# leds.net
KiCad netlist of a schematic drawn in EAGLE
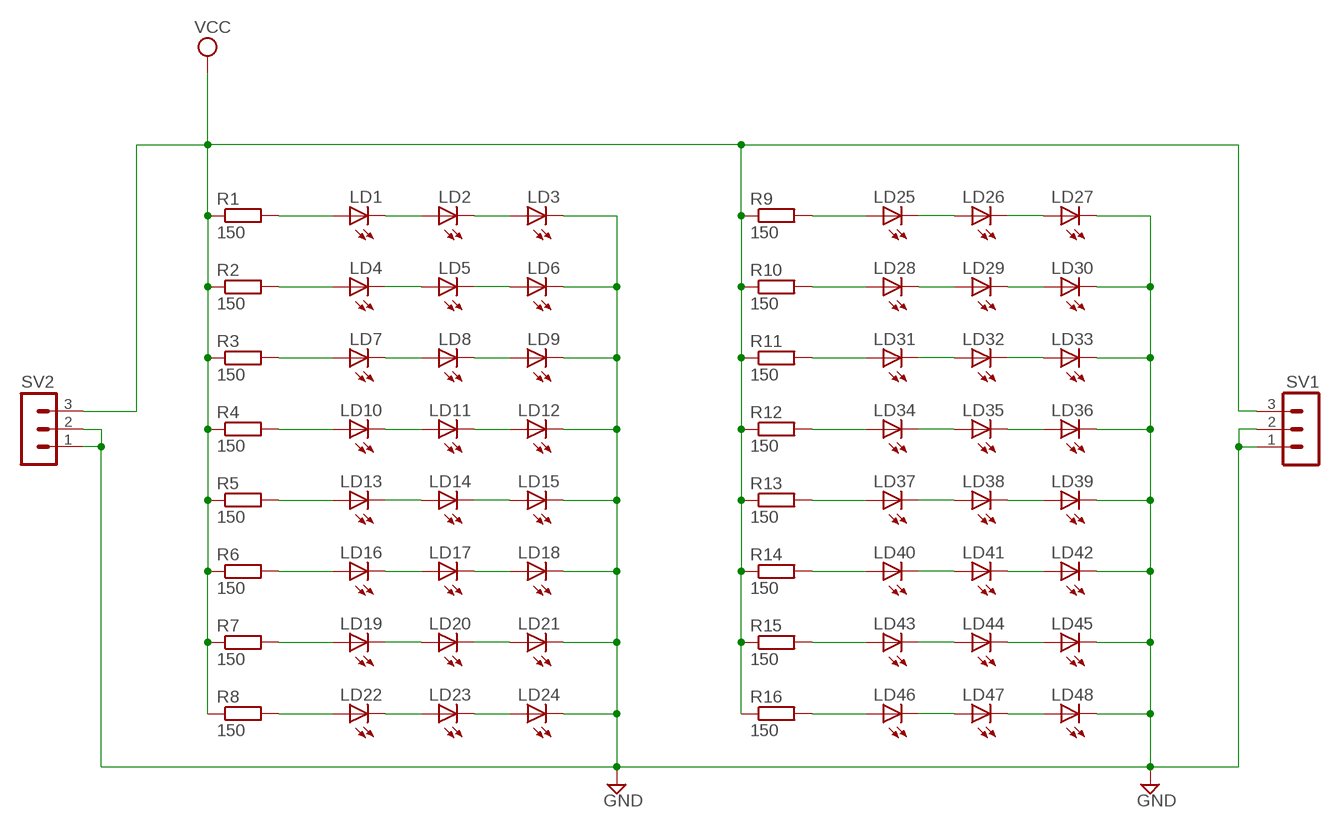
[diagram p0: schematic, sheet 1]

(export (version "E")
  (design (tool "Eeschema 10.0.6"))
  (components
    (comp (ref "LD1")
      (value "LED5MM")
      (footprint "eagle-import:LED5MM")
      (libsource (lib "eagle-import") (part "LED5MM"))
    )
    (comp (ref "LD2")
      (value "LED5MM")
      (footprint "eagle-import:LED5MM")
      (libsource (lib "eagle-import") (part "LED5MM"))
    )
    (comp (ref "LD3")
      (value "LED5MM")
      (footprint "eagle-import:LED5MM")
      (libsource (lib "eagle-import") (part "LED5MM"))
    )
    (comp (ref "LD4")
      (value "LED5MM")
      (footprint "eagle-import:LED5MM")
      (libsource (lib "eagle-import") (part "LED5MM"))
    )
    (comp (ref "LD5")
      (value "LED5MM")
      (footprint "eagle-import:LED5MM")
      (libsource (lib "eagle-import") (part "LED5MM"))
    )
    (comp (ref "LD6")
      (value "LED5MM")
      (footprint "eagle-import:LED5MM")
      (libsource (lib "eagle-import") (part "LED5MM"))
    )
    (comp (ref "LD7")
      (value "LED5MM")
      (footprint "eagle-import:LED5MM")
      (libsource (lib "eagle-import") (part "LED5MM"))
    )
    (comp (ref "LD8")
      (value "LED5MM")
      (footprint "eagle-import:LED5MM")
      (libsource (lib "eagle-import") (part "LED5MM"))
    )
    (comp (ref "LD9")
      (value "LED5MM")
      (footprint "eagle-import:LED5MM")
      (libsource (lib "eagle-import") (part "LED5MM"))
    )
    (comp (ref "LD10")
      (value "LED5MM")
      (footprint "eagle-import:LED5MM")
      (libsource (lib "eagle-import") (part "LED5MM"))
    )
    (comp (ref "LD11")
      (value "LED5MM")
      (footprint "eagle-import:LED5MM")
      (libsource (lib "eagle-import") (part "LED5MM"))
    )
    (comp (ref "LD12")
      (value "LED5MM")
      (footprint "eagle-import:LED5MM")
      (libsource (lib "eagle-import") (part "LED5MM"))
    )
    (comp (ref "LD13")
      (value "LED5MM")
      (footprint "eagle-import:LED5MM")
      (libsource (lib "eagle-import") (part "LED5MM"))
    )
    (comp (ref "LD14")
      (value "LED5MM")
      (footprint "eagle-import:LED5MM")
      (libsource (lib "eagle-import") (part "LED5MM"))
    )
    (comp (ref "LD15")
      (value "LED5MM")
      (footprint "eagle-import:LED5MM")
      (libsource (lib "eagle-import") (part "LED5MM"))
    )
    (comp (ref "LD16")
      (value "LED5MM")
      (footprint "eagle-import:LED5MM")
      (libsource (lib "eagle-import") (part "LED5MM"))
    )
    (comp (ref "LD17")
      (value "LED5MM")
      (footprint "eagle-import:LED5MM")
      (libsource (lib "eagle-import") (part "LED5MM"))
    )
    (comp (ref "LD18")
      (value "LED5MM")
      (footprint "eagle-import:LED5MM")
      (libsource (lib "eagle-import") (part "LED5MM"))
    )
    (comp (ref "LD19")
      (value "LED5MM")
      (footprint "eagle-import:LED5MM")
      (libsource (lib "eagle-import") (part "LED5MM"))
    )
    (comp (ref "LD20")
      (value "LED5MM")
      (footprint "eagle-import:LED5MM")
      (libsource (lib "eagle-import") (part "LED5MM"))
    )
    (comp (ref "LD21")
      (value "LED5MM")
      (footprint "eagle-import:LED5MM")
      (libsource (lib "eagle-import") (part "LED5MM"))
    )
    (comp (ref "LD22")
      (value "LED5MM")
      (footprint "eagle-import:LED5MM")
      (libsource (lib "eagle-import") (part "LED5MM"))
    )
    (comp (ref "LD23")
      (value "LED5MM")
      (footprint "eagle-import:LED5MM")
      (libsource (lib "eagle-import") (part "LED5MM"))
    )
    (comp (ref "LD24")
      (value "LED5MM")
      (footprint "eagle-import:LED5MM")
      (libsource (lib "eagle-import") (part "LED5MM"))
    )
    (comp (ref "LD25")
      (value "LED5MM")
      (footprint "eagle-import:LED5MM")
      (libsource (lib "eagle-import") (part "LED5MM"))
    )
    (comp (ref "LD26")
      (value "LED5MM")
      (footprint "eagle-import:LED5MM")
      (libsource (lib "eagle-import") (part "LED5MM"))
    )
    (comp (ref "LD27")
      (value "LED5MM")
      (footprint "eagle-import:LED5MM")
      (libsource (lib "eagle-import") (part "LED5MM"))
    )
    (comp (ref "LD28")
      (value "LED5MM")
      (footprint "eagle-import:LED5MM")
      (libsource (lib "eagle-import") (part "LED5MM"))
    )
    (comp (ref "LD29")
      (value "LED5MM")
      (footprint "eagle-import:LED5MM")
      (libsource (lib "eagle-import") (part "LED5MM"))
    )
    (comp (ref "LD30")
      (value "LED5MM")
      (footprint "eagle-import:LED5MM")
      (libsource (lib "eagle-import") (part "LED5MM"))
    )
    (comp (ref "LD31")
      (value "LED5MM")
      (footprint "eagle-import:LED5MM")
      (libsource (lib "eagle-import") (part "LED5MM"))
    )
    (comp (ref "LD32")
      (value "LED5MM")
      (footprint "eagle-import:LED5MM")
      (libsource (lib "eagle-import") (part "LED5MM"))
    )
    (comp (ref "LD33")
      (value "LED5MM")
      (footprint "eagle-import:LED5MM")
      (libsource (lib "eagle-import") (part "LED5MM"))
    )
    (comp (ref "LD34")
      (value "LED5MM")
      (footprint "eagle-import:LED5MM")
      (libsource (lib "eagle-import") (part "LED5MM"))
    )
    (comp (ref "LD35")
      (value "LED5MM")
      (footprint "eagle-import:LED5MM")
      (libsource (lib "eagle-import") (part "LED5MM"))
    )
    (comp (ref "LD36")
      (value "LED5MM")
      (footprint "eagle-import:LED5MM")
      (libsource (lib "eagle-import") (part "LED5MM"))
    )
    (comp (ref "LD37")
      (value "LED5MM")
      (footprint "eagle-import:LED5MM")
      (libsource (lib "eagle-import") (part "LED5MM"))
    )
    (comp (ref "LD38")
      (value "LED5MM")
      (footprint "eagle-import:LED5MM")
      (libsource (lib "eagle-import") (part "LED5MM"))
    )
    (comp (ref "LD39")
      (value "LED5MM")
      (footprint "eagle-import:LED5MM")
      (libsource (lib "eagle-import") (part "LED5MM"))
    )
    (comp (ref "LD40")
      (value "LED5MM")
      (footprint "eagle-import:LED5MM")
      (libsource (lib "eagle-import") (part "LED5MM"))
    )
    (comp (ref "LD41")
      (value "LED5MM")
      (footprint "eagle-import:LED5MM")
      (libsource (lib "eagle-import") (part "LED5MM"))
    )
    (comp (ref "LD42")
      (value "LED5MM")
      (footprint "eagle-import:LED5MM")
      (libsource (lib "eagle-import") (part "LED5MM"))
    )
    (comp (ref "LD43")
      (value "LED5MM")
      (footprint "eagle-import:LED5MM")
      (libsource (lib "eagle-import") (part "LED5MM"))
    )
    (comp (ref "LD44")
      (value "LED5MM")
      (footprint "eagle-import:LED5MM")
      (libsource (lib "eagle-import") (part "LED5MM"))
    )
    (comp (ref "LD45")
      (value "LED5MM")
      (footprint "eagle-import:LED5MM")
      (libsource (lib "eagle-import") (part "LED5MM"))
    )
    (comp (ref "LD46")
      (value "LED5MM")
      (footprint "eagle-import:LED5MM")
      (libsource (lib "eagle-import") (part "LED5MM"))
    )
    (comp (ref "LD47")
      (value "LED5MM")
      (footprint "eagle-import:LED5MM")
      (libsource (lib "eagle-import") (part "LED5MM"))
    )
    (comp (ref "LD48")
      (value "LED5MM")
      (footprint "eagle-import:LED5MM")
      (libsource (lib "eagle-import") (part "LED5MM"))
    )
    (comp (ref "R1")
      (value "150")
      (footprint "eagle-import:0204_7")
      (libsource (lib "eagle-import") (part "R-EU_0204/7"))
    )
    (comp (ref "R2")
      (value "150")
      (footprint "eagle-import:0204_7")
      (libsource (lib "eagle-import") (part "R-EU_0204/7"))
    )
    (comp (ref "R3")
      (value "150")
      (footprint "eagle-import:0204_7")
      (libsource (lib "eagle-import") (part "R-EU_0204/7"))
    )
    (comp (ref "R4")
      (value "150")
      (footprint "eagle-import:0204_7")
      (libsource (lib "eagle-import") (part "R-EU_0204/7"))
    )
    (comp (ref "R5")
      (value "150")
      (footprint "eagle-import:0204_7")
      (libsource (lib "eagle-import") (part "R-EU_0204/7"))
    )
    (comp (ref "R6")
      (value "150")
      (footprint "eagle-import:0204_7")
      (libsource (lib "eagle-import") (part "R-EU_0204/7"))
    )
    (comp (ref "R7")
      (value "150")
      (footprint "eagle-import:0204_7")
      (libsource (lib "eagle-import") (part "R-EU_0204/7"))
    )
    (comp (ref "R8")
      (value "150")
      (footprint "eagle-import:0204_7")
      (libsource (lib "eagle-import") (part "R-EU_0204/7"))
    )
    (comp (ref "R9")
      (value "150")
      (footprint "eagle-import:0204_7")
      (libsource (lib "eagle-import") (part "R-EU_0204/7"))
    )
    (comp (ref "R10")
      (value "150")
      (footprint "eagle-import:0204_7")
      (libsource (lib "eagle-import") (part "R-EU_0204/7"))
    )
    (comp (ref "R11")
      (value "150")
      (footprint "eagle-import:0204_7")
      (libsource (lib "eagle-import") (part "R-EU_0204/7"))
    )
    (comp (ref "R12")
      (value "150")
      (footprint "eagle-import:0204_7")
      (libsource (lib "eagle-import") (part "R-EU_0204/7"))
    )
    (comp (ref "R13")
      (value "150")
      (footprint "eagle-import:0204_7")
      (libsource (lib "eagle-import") (part "R-EU_0204/7"))
    )
    (comp (ref "R14")
      (value "150")
      (footprint "eagle-import:0204_7")
      (libsource (lib "eagle-import") (part "R-EU_0204/7"))
    )
    (comp (ref "R15")
      (value "150")
      (footprint "eagle-import:0204_7")
      (libsource (lib "eagle-import") (part "R-EU_0204/7"))
    )
    (comp (ref "R16")
      (value "150")
      (footprint "eagle-import:0204_7")
      (libsource (lib "eagle-import") (part "R-EU_0204/7"))
    )
    (comp (ref "SV1")
      (value "MA03-1")
      (footprint "eagle-import:MA03-1")
      (libsource (lib "eagle-import") (part "MA03-1"))
    )
    (comp (ref "SV2")
      (value "MA03-1")
      (footprint "eagle-import:MA03-1")
      (libsource (lib "eagle-import") (part "MA03-1"))
    )
  )
  (nets
    (net (code "1") (name "GND") (class "Default")
      (node (ref "LD12") (pin "K") (pinfunction "C_K") (pintype "passive"))
      (node (ref "LD15") (pin "K") (pinfunction "C_K") (pintype "passive"))
      (node (ref "LD18") (pin "K") (pinfunction "C_K") (pintype "passive"))
      (node (ref "LD21") (pin "K") (pinfunction "C_K") (pintype "passive"))
      (node (ref "LD24") (pin "K") (pinfunction "C_K") (pintype "passive"))
      (node (ref "LD27") (pin "K") (pinfunction "C_K") (pintype "passive"))
      (node (ref "LD3") (pin "K") (pinfunction "C_K") (pintype "passive"))
      (node (ref "LD30") (pin "K") (pinfunction "C_K") (pintype "passive"))
      (node (ref "LD33") (pin "K") (pinfunction "C_K") (pintype "passive"))
      (node (ref "LD36") (pin "K") (pinfunction "C_K") (pintype "passive"))
      (node (ref "LD39") (pin "K") (pinfunction "C_K") (pintype "passive"))
      (node (ref "LD42") (pin "K") (pinfunction "C_K") (pintype "passive"))
      (node (ref "LD45") (pin "K") (pinfunction "C_K") (pintype "passive"))
      (node (ref "LD48") (pin "K") (pinfunction "C_K") (pintype "passive"))
      (node (ref "LD6") (pin "K") (pinfunction "C_K") (pintype "passive"))
      (node (ref "LD9") (pin "K") (pinfunction "C_K") (pintype "passive"))
      (node (ref "SV1") (pin "1") (pinfunction "1_1") (pintype "passive"))
      (node (ref "SV1") (pin "2") (pinfunction "2_2") (pintype "passive"))
      (node (ref "SV2") (pin "1") (pinfunction "1_1") (pintype "passive"))
      (node (ref "SV2") (pin "2") (pinfunction "2_2") (pintype "passive"))
    )
    (net (code "2") (name "Net-(LD1-C)") (class "Default")
      (node (ref "LD1") (pin "K") (pinfunction "C_K") (pintype "passive"))
      (node (ref "LD2") (pin "A") (pinfunction "A_A") (pintype "passive"))
    )
    (net (code "3") (name "Net-(LD1-PadA)") (class "Default")
      (node (ref "LD1") (pin "A") (pinfunction "A_A") (pintype "passive"))
      (node (ref "R1") (pin "2") (pinfunction "2_2") (pintype "passive"))
    )
    (net (code "4") (name "Net-(LD2-C)") (class "Default")
      (node (ref "LD2") (pin "K") (pinfunction "C_K") (pintype "passive"))
      (node (ref "LD3") (pin "A") (pinfunction "A_A") (pintype "passive"))
    )
    (net (code "5") (name "Net-(LD4-C)") (class "Default")
      (node (ref "LD4") (pin "K") (pinfunction "C_K") (pintype "passive"))
      (node (ref "LD5") (pin "A") (pinfunction "A_A") (pintype "passive"))
    )
    (net (code "6") (name "Net-(LD4-PadA)") (class "Default")
      (node (ref "LD4") (pin "A") (pinfunction "A_A") (pintype "passive"))
      (node (ref "R2") (pin "2") (pinfunction "2_2") (pintype "passive"))
    )
    (net (code "7") (name "Net-(LD5-C)") (class "Default")
      (node (ref "LD5") (pin "K") (pinfunction "C_K") (pintype "passive"))
      (node (ref "LD6") (pin "A") (pinfunction "A_A") (pintype "passive"))
    )
    (net (code "8") (name "Net-(LD7-C)") (class "Default")
      (node (ref "LD7") (pin "K") (pinfunction "C_K") (pintype "passive"))
      (node (ref "LD8") (pin "A") (pinfunction "A_A") (pintype "passive"))
    )
    (net (code "9") (name "Net-(LD7-PadA)") (class "Default")
      (node (ref "LD7") (pin "A") (pinfunction "A_A") (pintype "passive"))
      (node (ref "R3") (pin "2") (pinfunction "2_2") (pintype "passive"))
    )
    (net (code "10") (name "Net-(LD8-C)") (class "Default")
      (node (ref "LD8") (pin "K") (pinfunction "C_K") (pintype "passive"))
      (node (ref "LD9") (pin "A") (pinfunction "A_A") (pintype "passive"))
    )
    (net (code "11") (name "Net-(LD10-C)") (class "Default")
      (node (ref "LD10") (pin "K") (pinfunction "C_K") (pintype "passive"))
      (node (ref "LD11") (pin "A") (pinfunction "A_A") (pintype "passive"))
    )
    (net (code "12") (name "Net-(LD10-PadA)") (class "Default")
      (node (ref "LD10") (pin "A") (pinfunction "A_A") (pintype "passive"))
      (node (ref "R4") (pin "2") (pinfunction "2_2") (pintype "passive"))
    )
    (net (code "13") (name "Net-(LD11-C)") (class "Default")
      (node (ref "LD11") (pin "K") (pinfunction "C_K") (pintype "passive"))
      (node (ref "LD12") (pin "A") (pinfunction "A_A") (pintype "passive"))
    )
    (net (code "14") (name "Net-(LD13-C)") (class "Default")
      (node (ref "LD13") (pin "K") (pinfunction "C_K") (pintype "passive"))
      (node (ref "LD14") (pin "A") (pinfunction "A_A") (pintype "passive"))
    )
    (net (code "15") (name "Net-(LD13-PadA)") (class "Default")
      (node (ref "LD13") (pin "A") (pinfunction "A_A") (pintype "passive"))
      (node (ref "R5") (pin "2") (pinfunction "2_2") (pintype "passive"))
    )
    (net (code "16") (name "Net-(LD14-C)") (class "Default")
      (node (ref "LD14") (pin "K") (pinfunction "C_K") (pintype "passive"))
      (node (ref "LD15") (pin "A") (pinfunction "A_A") (pintype "passive"))
    )
    (net (code "17") (name "Net-(LD16-C)") (class "Default")
      (node (ref "LD16") (pin "K") (pinfunction "C_K") (pintype "passive"))
      (node (ref "LD17") (pin "A") (pinfunction "A_A") (pintype "passive"))
    )
    (net (code "18") (name "Net-(LD16-PadA)") (class "Default")
      (node (ref "LD16") (pin "A") (pinfunction "A_A") (pintype "passive"))
      (node (ref "R6") (pin "2") (pinfunction "2_2") (pintype "passive"))
    )
    (net (code "19") (name "Net-(LD17-C)") (class "Default")
      (node (ref "LD17") (pin "K") (pinfunction "C_K") (pintype "passive"))
      (node (ref "LD18") (pin "A") (pinfunction "A_A") (pintype "passive"))
    )
    (net (code "20") (name "Net-(LD19-C)") (class "Default")
      (node (ref "LD19") (pin "K") (pinfunction "C_K") (pintype "passive"))
      (node (ref "LD20") (pin "A") (pinfunction "A_A") (pintype "passive"))
    )
    (net (code "21") (name "Net-(LD19-PadA)") (class "Default")
      (node (ref "LD19") (pin "A") (pinfunction "A_A") (pintype "passive"))
      (node (ref "R7") (pin "2") (pinfunction "2_2") (pintype "passive"))
    )
    (net (code "22") (name "Net-(LD20-C)") (class "Default")
      (node (ref "LD20") (pin "K") (pinfunction "C_K") (pintype "passive"))
      (node (ref "LD21") (pin "A") (pinfunction "A_A") (pintype "passive"))
    )
    (net (code "23") (name "Net-(LD22-C)") (class "Default")
      (node (ref "LD22") (pin "K") (pinfunction "C_K") (pintype "passive"))
      (node (ref "LD23") (pin "A") (pinfunction "A_A") (pintype "passive"))
    )
    (net (code "24") (name "Net-(LD22-PadA)") (class "Default")
      (node (ref "LD22") (pin "A") (pinfunction "A_A") (pintype "passive"))
      (node (ref "R8") (pin "2") (pinfunction "2_2") (pintype "passive"))
    )
    (net (code "25") (name "Net-(LD23-C)") (class "Default")
      (node (ref "LD23") (pin "K") (pinfunction "C_K") (pintype "passive"))
      (node (ref "LD24") (pin "A") (pinfunction "A_A") (pintype "passive"))
    )
    (net (code "26") (name "Net-(LD25-C)") (class "Default")
      (node (ref "LD25") (pin "K") (pinfunction "C_K") (pintype "passive"))
      (node (ref "LD26") (pin "A") (pinfunction "A_A") (pintype "passive"))
    )
    (net (code "27") (name "Net-(LD25-PadA)") (class "Default")
      (node (ref "LD25") (pin "A") (pinfunction "A_A") (pintype "passive"))
      (node (ref "R9") (pin "2") (pinfunction "2_2") (pintype "passive"))
    )
    (net (code "28") (name "Net-(LD26-C)") (class "Default")
      (node (ref "LD26") (pin "K") (pinfunction "C_K") (pintype "passive"))
      (node (ref "LD27") (pin "A") (pinfunction "A_A") (pintype "passive"))
    )
    (net (code "29") (name "Net-(LD28-C)") (class "Default")
      (node (ref "LD28") (pin "K") (pinfunction "C_K") (pintype "passive"))
      (node (ref "LD29") (pin "A") (pinfunction "A_A") (pintype "passive"))
    )
    (net (code "30") (name "Net-(LD28-PadA)") (class "Default")
      (node (ref "LD28") (pin "A") (pinfunction "A_A") (pintype "passive"))
      (node (ref "R10") (pin "2") (pinfunction "2_2") (pintype "passive"))
    )
    (net (code "31") (name "Net-(LD29-C)") (class "Default")
      (node (ref "LD29") (pin "K") (pinfunction "C_K") (pintype "passive"))
      (node (ref "LD30") (pin "A") (pinfunction "A_A") (pintype "passive"))
    )
    (net (code "32") (name "Net-(LD31-C)") (class "Default")
      (node (ref "LD31") (pin "K") (pinfunction "C_K") (pintype "passive"))
      (node (ref "LD32") (pin "A") (pinfunction "A_A") (pintype "passive"))
    )
    (net (code "33") (name "Net-(LD31-PadA)") (class "Default")
      (node (ref "LD31") (pin "A") (pinfunction "A_A") (pintype "passive"))
      (node (ref "R11") (pin "2") (pinfunction "2_2") (pintype "passive"))
    )
    (net (code "34") (name "Net-(LD32-C)") (class "Default")
      (node (ref "LD32") (pin "K") (pinfunction "C_K") (pintype "passive"))
      (node (ref "LD33") (pin "A") (pinfunction "A_A") (pintype "passive"))
    )
    (net (code "35") (name "Net-(LD34-C)") (class "Default")
      (node (ref "LD34") (pin "K") (pinfunction "C_K") (pintype "passive"))
      (node (ref "LD35") (pin "A") (pinfunction "A_A") (pintype "passive"))
    )
    (net (code "36") (name "Net-(LD34-PadA)") (class "Default")
      (node (ref "LD34") (pin "A") (pinfunction "A_A") (pintype "passive"))
      (node (ref "R12") (pin "2") (pinfunction "2_2") (pintype "passive"))
    )
    (net (code "37") (name "Net-(LD35-C)") (class "Default")
      (node (ref "LD35") (pin "K") (pinfunction "C_K") (pintype "passive"))
      (node (ref "LD36") (pin "A") (pinfunction "A_A") (pintype "passive"))
    )
    (net (code "38") (name "Net-(LD37-C)") (class "Default")
      (node (ref "LD37") (pin "K") (pinfunction "C_K") (pintype "passive"))
      (node (ref "LD38") (pin "A") (pinfunction "A_A") (pintype "passive"))
    )
    (net (code "39") (name "Net-(LD37-PadA)") (class "Default")
      (node (ref "LD37") (pin "A") (pinfunction "A_A") (pintype "passive"))
      (node (ref "R13") (pin "2") (pinfunction "2_2") (pintype "passive"))
    )
    (net (code "40") (name "Net-(LD38-C)") (class "Default")
      (node (ref "LD38") (pin "K") (pinfunction "C_K") (pintype "passive"))
      (node (ref "LD39") (pin "A") (pinfunction "A_A") (pintype "passive"))
    )
    (net (code "41") (name "Net-(LD40-C)") (class "Default")
      (node (ref "LD40") (pin "K") (pinfunction "C_K") (pintype "passive"))
      (node (ref "LD41") (pin "A") (pinfunction "A_A") (pintype "passive"))
    )
    (net (code "42") (name "Net-(LD40-PadA)") (class "Default")
      (node (ref "LD40") (pin "A") (pinfunction "A_A") (pintype "passive"))
      (node (ref "R14") (pin "2") (pinfunction "2_2") (pintype "passive"))
    )
    (net (code "43") (name "Net-(LD41-C)") (class "Default")
      (node (ref "LD41") (pin "K") (pinfunction "C_K") (pintype "passive"))
      (node (ref "LD42") (pin "A") (pinfunction "A_A") (pintype "passive"))
    )
    (net (code "44") (name "Net-(LD43-C)") (class "Default")
      (node (ref "LD43") (pin "K") (pinfunction "C_K") (pintype "passive"))
      (node (ref "LD44") (pin "A") (pinfunction "A_A") (pintype "passive"))
    )
    (net (code "45") (name "Net-(LD43-PadA)") (class "Default")
      (node (ref "LD43") (pin "A") (pinfunction "A_A") (pintype "passive"))
      (node (ref "R15") (pin "2") (pinfunction "2_2") (pintype "passive"))
    )
    (net (code "46") (name "Net-(LD44-C)") (class "Default")
      (node (ref "LD44") (pin "K") (pinfunction "C_K") (pintype "passive"))
      (node (ref "LD45") (pin "A") (pinfunction "A_A") (pintype "passive"))
    )
    (net (code "47") (name "Net-(LD46-C)") (class "Default")
      (node (ref "LD46") (pin "K") (pinfunction "C_K") (pintype "passive"))
      (node (ref "LD47") (pin "A") (pinfunction "A_A") (pintype "passive"))
    )
    (net (code "48") (name "Net-(LD46-PadA)") (class "Default")
      (node (ref "LD46") (pin "A") (pinfunction "A_A") (pintype "passive"))
      (node (ref "R16") (pin "2") (pinfunction "2_2") (pintype "passive"))
    )
    (net (code "49") (name "Net-(LD47-C)") (class "Default")
      (node (ref "LD47") (pin "K") (pinfunction "C_K") (pintype "passive"))
      (node (ref "LD48") (pin "A") (pinfunction "A_A") (pintype "passive"))
    )
    (net (code "50") (name "VCC") (class "Default")
      (node (ref "R1") (pin "1") (pinfunction "1_1") (pintype "passive"))
      (node (ref "R10") (pin "1") (pinfunction "1_1") (pintype "passive"))
      (node (ref "R11") (pin "1") (pinfunction "1_1") (pintype "passive"))
      (node (ref "R12") (pin "1") (pinfunction "1_1") (pintype "passive"))
      (node (ref "R13") (pin "1") (pinfunction "1_1") (pintype "passive"))
      (node (ref "R14") (pin "1") (pinfunction "1_1") (pintype "passive"))
      (node (ref "R15") (pin "1") (pinfunction "1_1") (pintype "passive"))
      (node (ref "R16") (pin "1") (pinfunction "1_1") (pintype "passive"))
      (node (ref "R2") (pin "1") (pinfunction "1_1") (pintype "passive"))
      (node (ref "R3") (pin "1") (pinfunction "1_1") (pintype "passive"))
      (node (ref "R4") (pin "1") (pinfunction "1_1") (pintype "passive"))
      (node (ref "R5") (pin "1") (pinfunction "1_1") (pintype "passive"))
      (node (ref "R6") (pin "1") (pinfunction "1_1") (pintype "passive"))
      (node (ref "R7") (pin "1") (pinfunction "1_1") (pintype "passive"))
      (node (ref "R8") (pin "1") (pinfunction "1_1") (pintype "passive"))
      (node (ref "R9") (pin "1") (pinfunction "1_1") (pintype "passive"))
      (node (ref "SV1") (pin "3") (pinfunction "3_3") (pintype "passive"))
      (node (ref "SV2") (pin "3") (pinfunction "3_3") (pintype "passive"))
    )
  )
)
